# Sheet1.net
KiCad netlist of a schematic drawn in Altium Designer
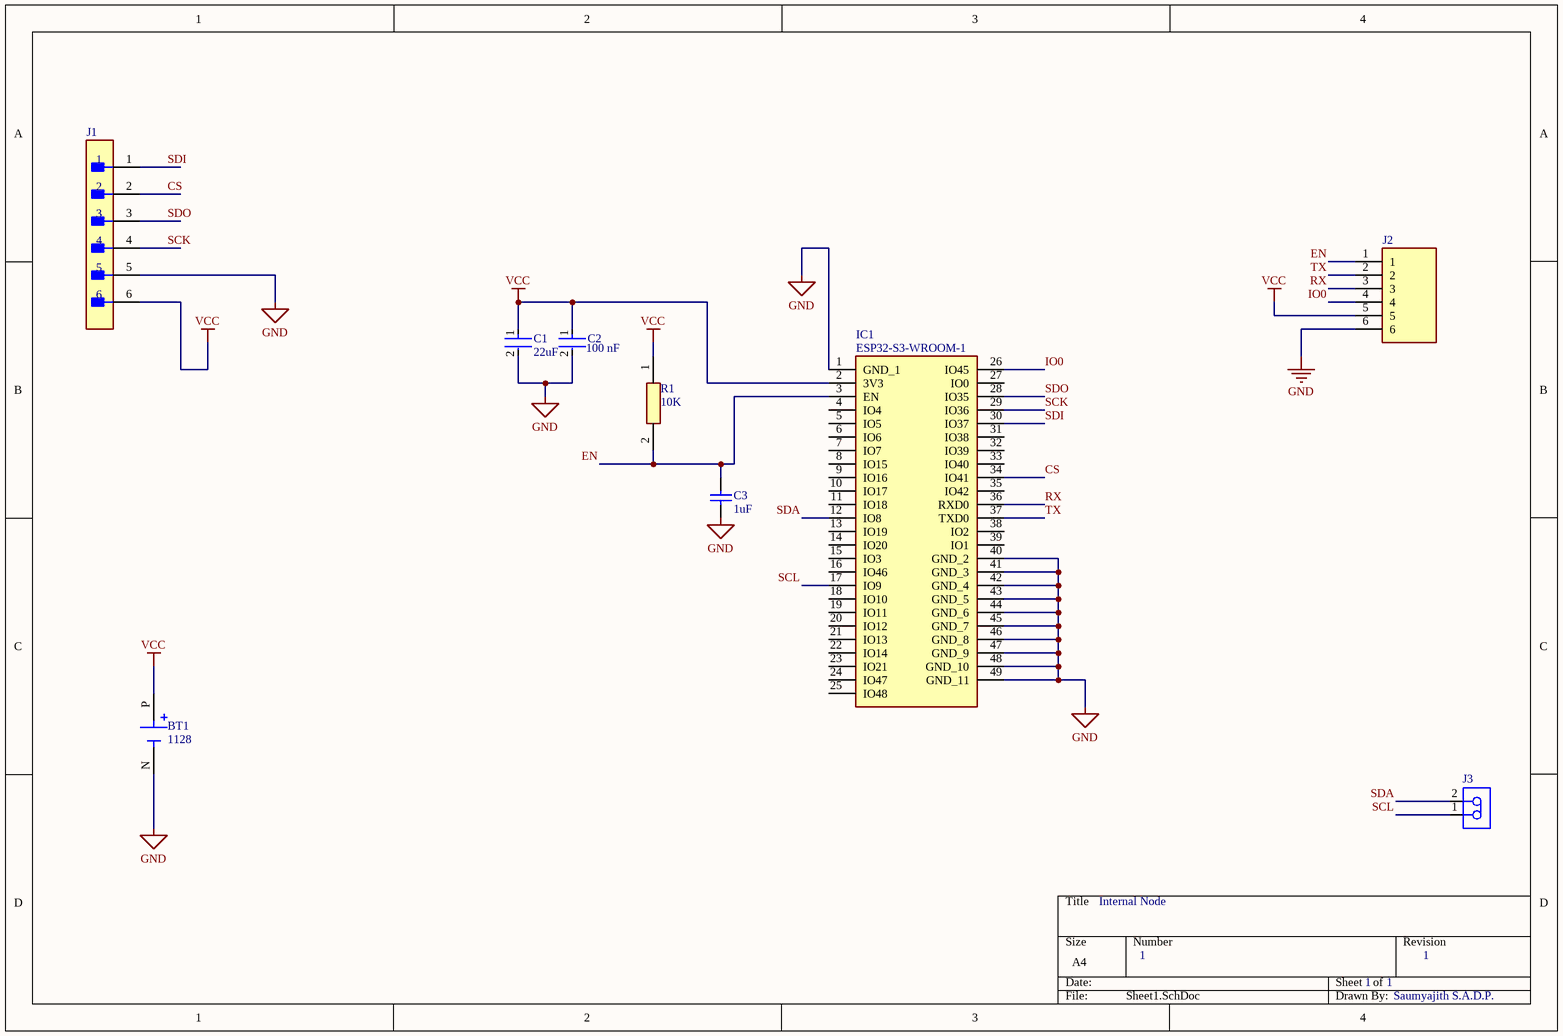
[diagram p0: Sheet1.SchDoc]

(export (version "E")
  (design (tool "Eeschema 10.0.6"))
  (components
    (comp (ref "BT1")
      (value "1128")
      (footprint "BAT_1128")
      (description "SMT Holder for CR123A Battery w/ coil spring")
      (fields (field (name "MF") "Keystone Electronics"))
      (libsource (lib "1128") (part "1128"))
    )
    (comp (ref "C1")
      (value "22uF")
      (footprint "FP-CL21-IPC_C")
      (description "CL21 Series 0805 22uF 16V ±20% Tolerance X5R Multilayer Ceramic Chip Capacitor")
      (fields (field (name "TOLERANCE") "20%"))
      (libsource (lib "Altium Content Vault") (part "b4654b650e69147ec39a6b967a45e02"))
    )
    (comp (ref "C2")
      (value "CC0805KRX7R7BB104")
      (footprint "FP-CC0805-0_85-MFG")
      (description "CAP CER 0.1UF 16V X7R 0805")
      (fields
        (field (name "MANUFACTURER") "Yageo")
        (field (name "OCTOPART") "https://octopart.com/cc0805krx7r7bb104-yageo-39467769")
        (field (name "CAPACITANCE") "100 nF")
      )
      (libsource (lib "Altium Content Vault") (part "11868f565c42a9108669ba33697ecf6"))
    )
    (comp (ref "C3")
      (value "1uF")
      (footprint "CAPC2013X140X50LL20T25")
      (fields
        (field (name "PART NUMBER") "0805ZC105KAZ2A")
        (field (name "MANUFACTURER") "AVX Interconnect / Elco")
      )
      (libsource (lib "Altium Content Vault") (part "CAP"))
    )
    (comp (ref "IC1")
      (value "ESP32-S3-WROOM-1")
      (footprint "SamacSys:ESP32S3WROOM1")
      (description "Integrated Circuit")
      (libsource (lib "*") (part "ESP32-S3-WROOM-1"))
    )
    (comp (ref "J1")
      (value "B6B-PH-K-K(LF)(SN)")
      (footprint "FP-B6B-PH-K-K_LF_SN-MFG")
      (description "PH Series 6 Position 2 mm Pitch Through Hole Top Entry Shrouded Header")
      (libsource (lib "Altium Content Vault") (part "f2cb566baf1c37ab5a3b8e90bbeafd6"))
    )
    (comp (ref "J2")
      (value "22-28-4060")
      (footprint "SamacSys:HDRV6W66P0X254_1X6_1524X249X838P")
      (description "Connector")
      (fields (field (name "MOUSER PART NUMBER") "538-22-28-4060"))
      (libsource (lib "*") (part "22-28-4060"))
    )
    (comp (ref "J3")
      (value "B2B-PH-K-S(LF)(SN)")
      (footprint "JST-B2B-PH-K-S_V")
      (fields (field (name "MANUFACTURER") "JST"))
      (libsource (lib "Altium Content Vault") (part "CN-2P-F-QF2"))
    )
    (comp (ref "R1")
      (value "10K")
      (footprint "SamacSys:RESC2012X60N")
      (description "Resistor")
      (fields
        (field (name "MANUFACTURER_PART_NUMBER") "CMP0805AFX-1002ELF")
        (field (name "MOUSER PART NUMBER") "652-CMP0805AFX-1002L")
      )
      (libsource (lib "*") (part "CMP0805AFX-1002ELF"))
    )
  )
  (nets
    (net (code "1") (name "/CS") (class "Default")
      (node (ref "IC1") (pin "34") (pinfunction "IO41_34") (pintype "passive"))
      (node (ref "J1") (pin "2") (pinfunction "2_2") (pintype "passive"))
    )
    (net (code "2") (name "/EN") (class "Default")
      (node (ref "C3") (pin "2") (pinfunction "2_2") (pintype "passive"))
      (node (ref "IC1") (pin "3") (pinfunction "EN_3") (pintype "passive"))
      (node (ref "J2") (pin "1") (pinfunction "1_1") (pintype "passive"))
      (node (ref "R1") (pin "2") (pinfunction "2_2") (pintype "passive"))
    )
    (net (code "3") (name "/IO0") (class "Default")
      (node (ref "IC1") (pin "26") (pinfunction "IO45_26") (pintype "passive"))
      (node (ref "J2") (pin "4") (pinfunction "4_4") (pintype "passive"))
    )
    (net (code "4") (name "/RX") (class "Default")
      (node (ref "IC1") (pin "36") (pinfunction "RXD0_36") (pintype "passive"))
      (node (ref "J2") (pin "3") (pinfunction "3_3") (pintype "passive"))
    )
    (net (code "5") (name "/SCK") (class "Default")
      (node (ref "IC1") (pin "29") (pinfunction "IO36_29") (pintype "passive"))
      (node (ref "J1") (pin "4") (pinfunction "4_4") (pintype "passive"))
    )
    (net (code "6") (name "/SCL") (class "Default")
      (node (ref "IC1") (pin "17") (pinfunction "IO9_17") (pintype "passive"))
      (node (ref "J3") (pin "1") (pinfunction "1_1") (pintype "passive"))
    )
    (net (code "7") (name "/SDA") (class "Default")
      (node (ref "IC1") (pin "12") (pinfunction "IO8_12") (pintype "passive"))
      (node (ref "J3") (pin "2") (pinfunction "2_2") (pintype "passive"))
    )
    (net (code "8") (name "/SDI") (class "Default")
      (node (ref "IC1") (pin "30") (pinfunction "IO37_30") (pintype "passive"))
      (node (ref "J1") (pin "1") (pinfunction "1_1") (pintype "passive"))
    )
    (net (code "9") (name "/SDO") (class "Default")
      (node (ref "IC1") (pin "28") (pinfunction "IO35_28") (pintype "passive"))
      (node (ref "J1") (pin "3") (pinfunction "3_3") (pintype "passive"))
    )
    (net (code "10") (name "/TX") (class "Default")
      (node (ref "IC1") (pin "37") (pinfunction "TXD0_37") (pintype "passive"))
      (node (ref "J2") (pin "2") (pinfunction "2_2") (pintype "passive"))
    )
    (net (code "11") (name "GND") (class "Default")
      (node (ref "BT1") (pin "N") (pinfunction "NEG_N") (pintype "passive"))
      (node (ref "C1") (pin "2") (pinfunction "2_2") (pintype "passive"))
      (node (ref "C2") (pin "2") (pinfunction "2_2") (pintype "passive"))
      (node (ref "C3") (pin "1") (pinfunction "1_1") (pintype "passive"))
      (node (ref "IC1") (pin "1") (pinfunction "GND_1_1") (pintype "passive"))
      (node (ref "IC1") (pin "40") (pinfunction "GND_2_40") (pintype "passive"))
      (node (ref "IC1") (pin "41") (pinfunction "GND_3_41") (pintype "passive"))
      (node (ref "IC1") (pin "42") (pinfunction "GND_4_42") (pintype "passive"))
      (node (ref "IC1") (pin "43") (pinfunction "GND_5_43") (pintype "passive"))
      (node (ref "IC1") (pin "44") (pinfunction "GND_6_44") (pintype "passive"))
      (node (ref "IC1") (pin "45") (pinfunction "GND_7_45") (pintype "passive"))
      (node (ref "IC1") (pin "46") (pinfunction "GND_8_46") (pintype "passive"))
      (node (ref "IC1") (pin "47") (pinfunction "GND_9_47") (pintype "passive"))
      (node (ref "IC1") (pin "48") (pinfunction "GND_10_48") (pintype "passive"))
      (node (ref "IC1") (pin "49") (pinfunction "GND_11_49") (pintype "passive"))
      (node (ref "J1") (pin "5") (pinfunction "5_5") (pintype "passive"))
      (node (ref "J2") (pin "6") (pinfunction "6_6") (pintype "passive"))
    )
    (net (code "12") (name "VCC") (class "Default")
      (node (ref "BT1") (pin "P") (pinfunction "POS_P") (pintype "passive"))
      (node (ref "C1") (pin "1") (pinfunction "1_1") (pintype "passive"))
      (node (ref "C2") (pin "1") (pinfunction "1_1") (pintype "passive"))
      (node (ref "IC1") (pin "2") (pinfunction "3V3_2") (pintype "passive"))
      (node (ref "J1") (pin "6") (pinfunction "6_6") (pintype "passive"))
      (node (ref "J2") (pin "5") (pinfunction "5_5") (pintype "passive"))
      (node (ref "R1") (pin "1") (pinfunction "1_1") (pintype "passive"))
    )
    (net (code "13") (name "unconnected-(IC1-IO0-Pad27)") (class "Default")
      (node (ref "IC1") (pin "27") (pinfunction "IO0_27") (pintype "passive"))
    )
    (net (code "14") (name "unconnected-(IC1-IO1-Pad39)") (class "Default")
      (node (ref "IC1") (pin "39") (pinfunction "IO1_39") (pintype "passive"))
    )
    (net (code "15") (name "unconnected-(IC1-IO2-Pad38)") (class "Default")
      (node (ref "IC1") (pin "38") (pinfunction "IO2_38") (pintype "passive"))
    )
    (net (code "16") (name "unconnected-(IC1-IO3-Pad15)") (class "Default")
      (node (ref "IC1") (pin "15") (pinfunction "IO3_15") (pintype "passive"))
    )
    (net (code "17") (name "unconnected-(IC1-IO4-Pad4)") (class "Default")
      (node (ref "IC1") (pin "4") (pinfunction "IO4_4") (pintype "passive"))
    )
    (net (code "18") (name "unconnected-(IC1-IO5-Pad5)") (class "Default")
      (node (ref "IC1") (pin "5") (pinfunction "IO5_5") (pintype "passive"))
    )
    (net (code "19") (name "unconnected-(IC1-IO6-Pad6)") (class "Default")
      (node (ref "IC1") (pin "6") (pinfunction "IO6_6") (pintype "passive"))
    )
    (net (code "20") (name "unconnected-(IC1-IO7-Pad7)") (class "Default")
      (node (ref "IC1") (pin "7") (pinfunction "IO7_7") (pintype "passive"))
    )
    (net (code "21") (name "unconnected-(IC1-IO10-Pad18)") (class "Default")
      (node (ref "IC1") (pin "18") (pinfunction "IO10_18") (pintype "passive"))
    )
    (net (code "22") (name "unconnected-(IC1-IO11-Pad19)") (class "Default")
      (node (ref "IC1") (pin "19") (pinfunction "IO11_19") (pintype "passive"))
    )
    (net (code "23") (name "unconnected-(IC1-IO12-Pad20)") (class "Default")
      (node (ref "IC1") (pin "20") (pinfunction "IO12_20") (pintype "passive"))
    )
    (net (code "24") (name "unconnected-(IC1-IO13-Pad21)") (class "Default")
      (node (ref "IC1") (pin "21") (pinfunction "IO13_21") (pintype "passive"))
    )
    (net (code "25") (name "unconnected-(IC1-IO14-Pad22)") (class "Default")
      (node (ref "IC1") (pin "22") (pinfunction "IO14_22") (pintype "passive"))
    )
    (net (code "26") (name "unconnected-(IC1-IO15-Pad8)") (class "Default")
      (node (ref "IC1") (pin "8") (pinfunction "IO15_8") (pintype "passive"))
    )
    (net (code "27") (name "unconnected-(IC1-IO16-Pad9)") (class "Default")
      (node (ref "IC1") (pin "9") (pinfunction "IO16_9") (pintype "passive"))
    )
    (net (code "28") (name "unconnected-(IC1-IO17-Pad10)") (class "Default")
      (node (ref "IC1") (pin "10") (pinfunction "IO17_10") (pintype "passive"))
    )
    (net (code "29") (name "unconnected-(IC1-IO18-Pad11)") (class "Default")
      (node (ref "IC1") (pin "11") (pinfunction "IO18_11") (pintype "passive"))
    )
    (net (code "30") (name "unconnected-(IC1-IO19-Pad13)") (class "Default")
      (node (ref "IC1") (pin "13") (pinfunction "IO19_13") (pintype "passive"))
    )
    (net (code "31") (name "unconnected-(IC1-IO20-Pad14)") (class "Default")
      (node (ref "IC1") (pin "14") (pinfunction "IO20_14") (pintype "passive"))
    )
    (net (code "32") (name "unconnected-(IC1-IO21-Pad23)") (class "Default")
      (node (ref "IC1") (pin "23") (pinfunction "IO21_23") (pintype "passive"))
    )
    (net (code "33") (name "unconnected-(IC1-IO38-Pad31)") (class "Default")
      (node (ref "IC1") (pin "31") (pinfunction "IO38_31") (pintype "passive"))
    )
    (net (code "34") (name "unconnected-(IC1-IO39-Pad32)") (class "Default")
      (node (ref "IC1") (pin "32") (pinfunction "IO39_32") (pintype "passive"))
    )
    (net (code "35") (name "unconnected-(IC1-IO40-Pad33)") (class "Default")
      (node (ref "IC1") (pin "33") (pinfunction "IO40_33") (pintype "passive"))
    )
    (net (code "36") (name "unconnected-(IC1-IO42-Pad35)") (class "Default")
      (node (ref "IC1") (pin "35") (pinfunction "IO42_35") (pintype "passive"))
    )
    (net (code "37") (name "unconnected-(IC1-IO46-Pad16)") (class "Default")
      (node (ref "IC1") (pin "16") (pinfunction "IO46_16") (pintype "passive"))
    )
    (net (code "38") (name "unconnected-(IC1-IO47-Pad24)") (class "Default")
      (node (ref "IC1") (pin "24") (pinfunction "IO47_24") (pintype "passive"))
    )
    (net (code "39") (name "unconnected-(IC1-IO48-Pad25)") (class "Default")
      (node (ref "IC1") (pin "25") (pinfunction "IO48_25") (pintype "passive"))
    )
  )
)
